# max31855-2.net
KiCad netlist of a schematic drawn in EAGLE
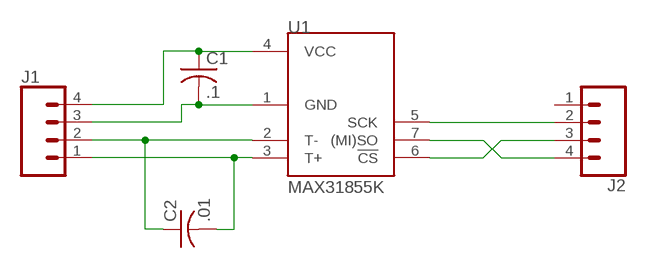
[diagram p0: schematic, sheet 1]

(export (version "E")
  (design (tool "Eeschema 10.0.6"))
  (components
    (comp (ref "C1")
      (value ".1")
      (footprint "eagle-import:C0805")
      (libsource (lib "eagle-import") (part "C-USC0805"))
    )
    (comp (ref "C2")
      (value ".01")
      (footprint "eagle-import:C0805")
      (libsource (lib "eagle-import") (part "C-USC0805"))
    )
    (comp (ref "J1")
      (value "CONN_04")
      (footprint "eagle-import:1X04")
      (libsource (lib "eagle-import") (part "CONN_04"))
    )
    (comp (ref "J2")
      (value "CONN_04")
      (footprint "eagle-import:1X04")
      (libsource (lib "eagle-import") (part "CONN_04"))
    )
    (comp (ref "U1")
      (value "MAX31855K")
      (footprint "eagle-import:SO08")
      (libsource (lib "eagle-import") (part "MAX31855K"))
    )
  )
  (nets
    (net (code "1") (name "Net-(U1-(MI)SO)") (class "Default")
      (node (ref "J2") (pin "4") (pinfunction "4_4") (pintype "passive"))
      (node (ref "U1") (pin "7") (pinfunction "(MI)SO_7") (pintype "bidirectional"))
    )
    (net (code "2") (name "Net-(U1-GND)") (class "Default")
      (node (ref "C1") (pin "2") (pinfunction "2_2") (pintype "passive"))
      (node (ref "J1") (pin "3") (pinfunction "3_3") (pintype "passive"))
      (node (ref "U1") (pin "1") (pinfunction "GND_1") (pintype "bidirectional"))
    )
    (net (code "3") (name "Net-(U1-SCK)") (class "Default")
      (node (ref "J2") (pin "2") (pinfunction "2_2") (pintype "passive"))
      (node (ref "U1") (pin "5") (pinfunction "SCK_5") (pintype "bidirectional"))
    )
    (net (code "4") (name "Net-(U1-T+)") (class "Default")
      (node (ref "C2") (pin "2") (pinfunction "2_2") (pintype "passive"))
      (node (ref "J1") (pin "1") (pinfunction "1_1") (pintype "passive"))
      (node (ref "U1") (pin "3") (pinfunction "T+_3") (pintype "bidirectional"))
    )
    (net (code "5") (name "Net-(U1-T-)") (class "Default")
      (node (ref "C2") (pin "1") (pinfunction "1_1") (pintype "passive"))
      (node (ref "J1") (pin "2") (pinfunction "2_2") (pintype "passive"))
      (node (ref "U1") (pin "2") (pinfunction "T-_2") (pintype "bidirectional"))
    )
    (net (code "6") (name "Net-(U1-VCC)") (class "Default")
      (node (ref "C1") (pin "1") (pinfunction "1_1") (pintype "passive"))
      (node (ref "J1") (pin "4") (pinfunction "4_4") (pintype "passive"))
      (node (ref "U1") (pin "4") (pinfunction "VCC_4") (pintype "bidirectional"))
    )
    (net (code "7") (name "Net-(U1-~{CS})") (class "Default")
      (node (ref "J2") (pin "3") (pinfunction "3_3") (pintype "passive"))
      (node (ref "U1") (pin "6") (pinfunction "~{CS}_6") (pintype "bidirectional"))
    )
    (net (code "8") (name "unconnected-(J2-Pad1)") (class "Default")
      (node (ref "J2") (pin "1") (pinfunction "1_1") (pintype "passive"))
    )
  )
)
